# Analog_Frontend01.net
KiCad netlist of a schematic drawn in Altium Designer
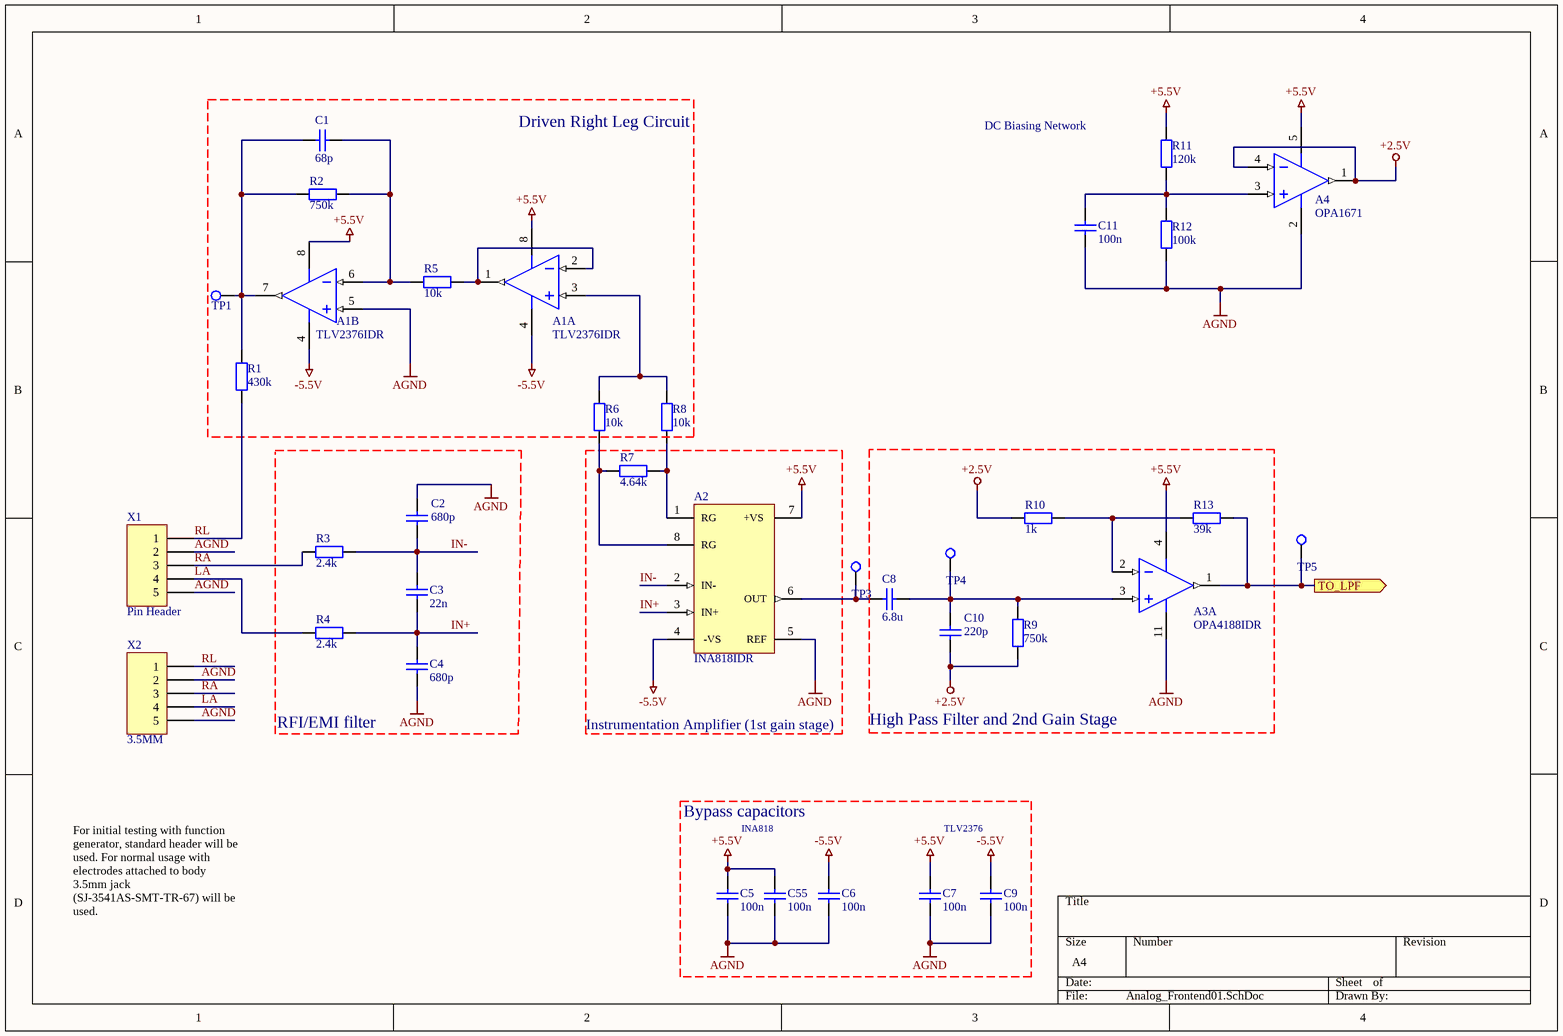
[diagram p0: Analog_Frontend01.SchDoc]

(export (version "E")
  (design (tool "Eeschema 10.0.6"))
  (components
    (comp (ref "A1")
      (value "TLV2376IDR")
      (footprint "SOIC127P600X175-8N")
      (libsource (lib "Analog Devices Operational Amplifiers") (part "AD706AR"))
    )
    (comp (ref "A2")
      (value "INA818IDR")
      (footprint "SOIC127P600X175-8N")
      (fields (field (name "MOUSER PART NUMBER") "595-INA818IDR"))
      (libsource (lib "Custom_Lib") (part "INAMP"))
    )
    (comp (ref "A3")
      (value "OPA4188IDR")
      (footprint "SOIC127P600X175-14N")
      (libsource (lib "Analog Devices Operational Amplifiers") (part "AD824ARZ-14-3V-RL"))
    )
    (comp (ref "A4")
      (value "OPA1671")
      (footprint "SOT95P280X145-5N")
      (libsource (lib "TI Amplifiers and Linear Operational Amplifier Precision Amplifier Part One") (part "OPA336NJ/250"))
    )
    (comp (ref "C1")
      (value "68p")
      (footprint "CAPC1608X87N")
      (libsource (lib "Miscellaneous Devices") (part "Cap"))
    )
    (comp (ref "C2")
      (value "680p")
      (footprint "CAPC2012X110N")
      (fields (field (name "MOUSER PART NUMBER") "667-ECH-U1H681GX5"))
      (libsource (lib "Miscellaneous Devices") (part "Cap"))
    )
    (comp (ref "C3")
      (value "22n")
      (footprint "CAPC3225X170N")
      (fields (field (name "MOUSER PART NUMBER") "667-ECH-U1H223GX5"))
      (libsource (lib "Miscellaneous Devices") (part "Cap"))
    )
    (comp (ref "C4")
      (value "680p")
      (footprint "CAPC2012X110N")
      (fields (field (name "MOUSER PART NUMBER") "667-ECH-U1H681GX5"))
      (libsource (lib "Miscellaneous Devices") (part "Cap"))
    )
    (comp (ref "C5")
      (value "100n")
      (footprint "CAPC1608X87N")
      (libsource (lib "Miscellaneous Devices") (part "Cap"))
    )
    (comp (ref "C6")
      (value "100n")
      (footprint "CAPC1608X87N")
      (libsource (lib "Miscellaneous Devices") (part "Cap"))
    )
    (comp (ref "C7")
      (value "100n")
      (footprint "CAPC1608X87N")
      (libsource (lib "Miscellaneous Devices") (part "Cap"))
    )
    (comp (ref "C8")
      (value "6.8u")
      (footprint "CAPC2012X110N")
      (libsource (lib "Miscellaneous Devices") (part "Cap"))
    )
    (comp (ref "C9")
      (value "100n")
      (footprint "CAPC1608X87N")
      (libsource (lib "Miscellaneous Devices") (part "Cap"))
    )
    (comp (ref "C10")
      (value "220p")
      (footprint "CAPC1608X87N")
      (libsource (lib "Miscellaneous Devices") (part "Cap"))
    )
    (comp (ref "C11")
      (value "100n")
      (footprint "CAPC1608X87N")
      (libsource (lib "Miscellaneous Devices") (part "Cap"))
    )
    (comp (ref "C55")
      (value "100n")
      (footprint "CAPC1608X87N")
      (description "Capacitor")
      (libsource (lib "Miscellaneous Devices") (part "Cap"))
    )
    (comp (ref "R1")
      (value "430k")
      (footprint "RESC1608X55N")
      (libsource (lib "Miscellaneous Devices") (part "Res2"))
    )
    (comp (ref "R2") (value "750k") (footprint "RESC1608X55N") (libsource (lib "") (part "Res2_1")))
    (comp (ref "R3")
      (value "2.4k")
      (footprint "RESC2012X70N")
      (fields (field (name "MOUSER PART NUMBER") "667-ERJ-6ENF2401V"))
      (libsource (lib "") (part "Res2_1"))
    )
    (comp (ref "R4")
      (value "2.4k")
      (footprint "RESC2012X70N")
      (fields (field (name "MOUSER PART NUMBER") "667-ERJ-6ENF2401V"))
      (libsource (lib "") (part "Res2_1"))
    )
    (comp (ref "R5")
      (value "10k")
      (footprint "RESC1608X55N")
      (fields (field (name "MOUSER PART NUMBER") "603-RC0603FR-0710KL"))
      (libsource (lib "") (part "Res2_1"))
    )
    (comp (ref "R6")
      (value "10k")
      (footprint "RESC1608X55N")
      (fields (field (name "MOUSER PART NUMBER") "603-RC0603FR-0710KL"))
      (libsource (lib "Miscellaneous Devices") (part "Res2"))
    )
    (comp (ref "R7")
      (value "4.64k")
      (footprint "RESC1608X55N")
      (libsource (lib "Miscellaneous Devices") (part "Res2"))
    )
    (comp (ref "R8")
      (value "10k")
      (footprint "RESC1608X55N")
      (fields (field (name "MOUSER PART NUMBER") "603-RC0603FR-0710KL"))
      (libsource (lib "Miscellaneous Devices") (part "Res2"))
    )
    (comp (ref "R9")
      (value "750k")
      (footprint "RESC1608X55N")
      (libsource (lib "Miscellaneous Devices") (part "Res2"))
    )
    (comp (ref "R10") (value "1k") (footprint "RESC1608X55N") (libsource (lib "") (part "Res2_1")))
    (comp (ref "R11") (value "120k") (footprint "RESC1608X55N") (libsource (lib "") (part "Res2_2")))
    (comp (ref "R12") (value "100k") (footprint "RESC1608X55N") (libsource (lib "") (part "Res2_2")))
    (comp (ref "R13") (value "39k") (footprint "RESC1608X55N") (libsource (lib "") (part "Res2_1")))
    (comp (ref "TP1")
      (value "TP")
      (footprint "TEST-POINT")
      (description "Generic test point")
      (libsource (lib "Custom_Lib") (part "TEST_POINT"))
    )
    (comp (ref "TP3")
      (value "TP")
      (footprint "TEST-POINT")
      (description "Generic test point")
      (libsource (lib "Custom_Lib") (part "TEST_POINT"))
    )
    (comp (ref "TP4")
      (value "TP")
      (footprint "TEST-POINT")
      (description "Generic test point")
      (libsource (lib "Custom_Lib") (part "TEST_POINT"))
    )
    (comp (ref "TP5")
      (value "TP")
      (footprint "TEST-POINT")
      (description "Generic test point")
      (libsource (lib "Custom_Lib") (part "TEST_POINT"))
    )
    (comp (ref "X1")
      (value "Pin Header")
      (footprint "SHDR5W64P0X250_1X5_1496X650X700P")
      (description "Header, 5-Pin")
      (libsource (lib "Miscellaneous Connectors") (part "Header 5"))
    )
    (comp (ref "X2")
      (value "3.5MM")
      (footprint "SJ23574ASMTTR")
      (description "Header, 5-Pin")
      (libsource (lib "Miscellaneous Connectors") (part "Header 5"))
    )
  )
  (nets
    (net (code "1") (name "+2.5V") (class "Default")
      (node (ref "A4") (pin "1") (pinfunction "OUT_1") (pintype "output"))
      (node (ref "A4") (pin "4") (pinfunction "IN-_4") (pintype "input"))
      (node (ref "C10") (pin "1") (pinfunction "1_1") (pintype "passive"))
      (node (ref "R10") (pin "1") (pinfunction "1_1") (pintype "passive"))
      (node (ref "R9") (pin "1") (pinfunction "1_1") (pintype "passive"))
    )
    (net (code "2") (name "+5.5V") (class "Default")
      (node (ref "A1") (pin "8") (pinfunction "+V_8") (pintype "power_in"))
      (node (ref "A2") (pin "7") (pinfunction "+VS_7") (pintype "power_in"))
      (node (ref "A3") (pin "4") (pinfunction "+V_4") (pintype "power_in"))
      (node (ref "A4") (pin "5") (pinfunction "V+_5") (pintype "power_in"))
      (node (ref "C5") (pin "2") (pinfunction "2_2") (pintype "passive"))
      (node (ref "C55") (pin "2") (pinfunction "2_2") (pintype "passive"))
      (node (ref "C7") (pin "2") (pinfunction "2_2") (pintype "passive"))
      (node (ref "R11") (pin "1") (pinfunction "1_1") (pintype "passive"))
    )
    (net (code "3") (name "-5.5V") (class "Default")
      (node (ref "A1") (pin "4") (pinfunction "-V_4") (pintype "power_in"))
      (node (ref "A2") (pin "4") (pinfunction "-VS_4") (pintype "power_in"))
      (node (ref "C6") (pin "2") (pinfunction "2_2") (pintype "passive"))
      (node (ref "C9") (pin "2") (pinfunction "2_2") (pintype "passive"))
    )
    (net (code "4") (name "/IN+") (class "Default")
      (node (ref "A2") (pin "3") (pinfunction "IN+_3") (pintype "input"))
      (node (ref "C3") (pin "1") (pinfunction "1_1") (pintype "passive"))
      (node (ref "C4") (pin "2") (pinfunction "2_2") (pintype "passive"))
      (node (ref "R4") (pin "2") (pinfunction "2_2") (pintype "passive"))
    )
    (net (code "5") (name "/IN-") (class "Default")
      (node (ref "A2") (pin "2") (pinfunction "IN-_2") (pintype "input"))
      (node (ref "C2") (pin "1") (pinfunction "1_1") (pintype "passive"))
      (node (ref "C3") (pin "2") (pinfunction "2_2") (pintype "passive"))
      (node (ref "R3") (pin "2") (pinfunction "2_2") (pintype "passive"))
    )
    (net (code "6") (name "/LA") (class "Default")
      (node (ref "R4") (pin "1") (pinfunction "1_1") (pintype "passive"))
      (node (ref "X1") (pin "4") (pinfunction "4_4") (pintype "passive"))
      (node (ref "X2") (pin "4") (pinfunction "4_4") (pintype "passive"))
    )
    (net (code "7") (name "/RA") (class "Default")
      (node (ref "R3") (pin "1") (pinfunction "1_1") (pintype "passive"))
      (node (ref "X1") (pin "3") (pinfunction "3_3") (pintype "passive"))
      (node (ref "X2") (pin "3") (pinfunction "3_3") (pintype "passive"))
    )
    (net (code "8") (name "/RL") (class "Default")
      (node (ref "R1") (pin "1") (pinfunction "1_1") (pintype "passive"))
      (node (ref "X1") (pin "1") (pinfunction "1_1") (pintype "passive"))
      (node (ref "X2") (pin "1") (pinfunction "1_1") (pintype "passive"))
    )
    (net (code "9") (name "/TO_LPF") (class "Default")
      (node (ref "A3") (pin "1") (pinfunction "OUT_A_1") (pintype "output"))
      (node (ref "R13") (pin "2") (pinfunction "2_2") (pintype "passive"))
      (node (ref "TP5") (pin "0") (pinfunction "0_0") (pintype "passive"))
    )
    (net (code "10") (name "AGND") (class "Default")
      (node (ref "A1") (pin "5") (pinfunction "+IN_5") (pintype "input"))
      (node (ref "A2") (pin "5") (pinfunction "REF_5") (pintype "passive"))
      (node (ref "A3") (pin "11") (pinfunction "-V_11") (pintype "power_in"))
      (node (ref "A4") (pin "2") (pinfunction "V-_2") (pintype "power_in"))
      (node (ref "C11") (pin "1") (pinfunction "1_1") (pintype "passive"))
      (node (ref "C2") (pin "2") (pinfunction "2_2") (pintype "passive"))
      (node (ref "C4") (pin "1") (pinfunction "1_1") (pintype "passive"))
      (node (ref "C5") (pin "1") (pinfunction "1_1") (pintype "passive"))
      (node (ref "C55") (pin "1") (pinfunction "1_1") (pintype "passive"))
      (node (ref "C6") (pin "1") (pinfunction "1_1") (pintype "passive"))
      (node (ref "C7") (pin "1") (pinfunction "1_1") (pintype "passive"))
      (node (ref "C9") (pin "1") (pinfunction "1_1") (pintype "passive"))
      (node (ref "R12") (pin "2") (pinfunction "2_2") (pintype "passive"))
      (node (ref "X1") (pin "2") (pinfunction "2_2") (pintype "passive"))
      (node (ref "X1") (pin "5") (pinfunction "5_5") (pintype "passive"))
      (node (ref "X2") (pin "2") (pinfunction "2_2") (pintype "passive"))
      (node (ref "X2") (pin "5") (pinfunction "5_5") (pintype "passive"))
    )
    (net (code "11") (name "Net-(A1A-+IN)") (class "Default")
      (node (ref "A1") (pin "3") (pinfunction "+IN_3") (pintype "input"))
      (node (ref "R6") (pin "2") (pinfunction "2_2") (pintype "passive"))
      (node (ref "R8") (pin "2") (pinfunction "2_2") (pintype "passive"))
    )
    (net (code "12") (name "Net-(A1A--IN)") (class "Default")
      (node (ref "A1") (pin "1") (pinfunction "OUT_1") (pintype "output"))
      (node (ref "A1") (pin "2") (pinfunction "-IN_2") (pintype "input"))
      (node (ref "R5") (pin "2") (pinfunction "2_2") (pintype "passive"))
    )
    (net (code "13") (name "Net-(A1B--IN)") (class "Default")
      (node (ref "A1") (pin "6") (pinfunction "-IN_6") (pintype "input"))
      (node (ref "C1") (pin "1") (pinfunction "1_1") (pintype "passive"))
      (node (ref "R2") (pin "2") (pinfunction "2_2") (pintype "passive"))
      (node (ref "R5") (pin "1") (pinfunction "1_1") (pintype "passive"))
    )
    (net (code "14") (name "Net-(A1B-OUT)") (class "Default")
      (node (ref "A1") (pin "7") (pinfunction "OUT_7") (pintype "output"))
      (node (ref "C1") (pin "2") (pinfunction "2_2") (pintype "passive"))
      (node (ref "R1") (pin "2") (pinfunction "2_2") (pintype "passive"))
      (node (ref "R2") (pin "1") (pinfunction "1_1") (pintype "passive"))
      (node (ref "TP1") (pin "0") (pinfunction "0_0") (pintype "passive"))
    )
    (net (code "15") (name "Net-(A2-OUT)") (class "Default")
      (node (ref "A2") (pin "6") (pinfunction "OUT_6") (pintype "output"))
      (node (ref "C8") (pin "2") (pinfunction "2_2") (pintype "passive"))
      (node (ref "TP3") (pin "0") (pinfunction "0_0") (pintype "passive"))
    )
    (net (code "16") (name "Net-(A2-RG-Pad1)") (class "Default")
      (node (ref "A2") (pin "1") (pinfunction "RG_1") (pintype "passive"))
      (node (ref "R7") (pin "2") (pinfunction "2_2") (pintype "passive"))
      (node (ref "R8") (pin "1") (pinfunction "1_1") (pintype "passive"))
    )
    (net (code "17") (name "Net-(A2-RG-Pad8)") (class "Default")
      (node (ref "A2") (pin "8") (pinfunction "RG_8") (pintype "passive"))
      (node (ref "R6") (pin "1") (pinfunction "1_1") (pintype "passive"))
      (node (ref "R7") (pin "1") (pinfunction "1_1") (pintype "passive"))
    )
    (net (code "18") (name "Net-(A3A-+IN_A)") (class "Default")
      (node (ref "A3") (pin "3") (pinfunction "+IN_A_3") (pintype "input"))
      (node (ref "C10") (pin "2") (pinfunction "2_2") (pintype "passive"))
      (node (ref "C8") (pin "1") (pinfunction "1_1") (pintype "passive"))
      (node (ref "R9") (pin "2") (pinfunction "2_2") (pintype "passive"))
      (node (ref "TP4") (pin "0") (pinfunction "0_0") (pintype "passive"))
    )
    (net (code "19") (name "Net-(A3A--IN_A)") (class "Default")
      (node (ref "A3") (pin "2") (pinfunction "-IN_A_2") (pintype "input"))
      (node (ref "R10") (pin "2") (pinfunction "2_2") (pintype "passive"))
      (node (ref "R13") (pin "1") (pinfunction "1_1") (pintype "passive"))
    )
    (net (code "20") (name "Net-(A4-IN+)") (class "Default")
      (node (ref "A4") (pin "3") (pinfunction "IN+_3") (pintype "input"))
      (node (ref "C11") (pin "2") (pinfunction "2_2") (pintype "passive"))
      (node (ref "R11") (pin "2") (pinfunction "2_2") (pintype "passive"))
      (node (ref "R12") (pin "1") (pinfunction "1_1") (pintype "passive"))
    )
  )
)
